# E-Book_v28.net
KiCad netlist of a schematic drawn in EAGLE
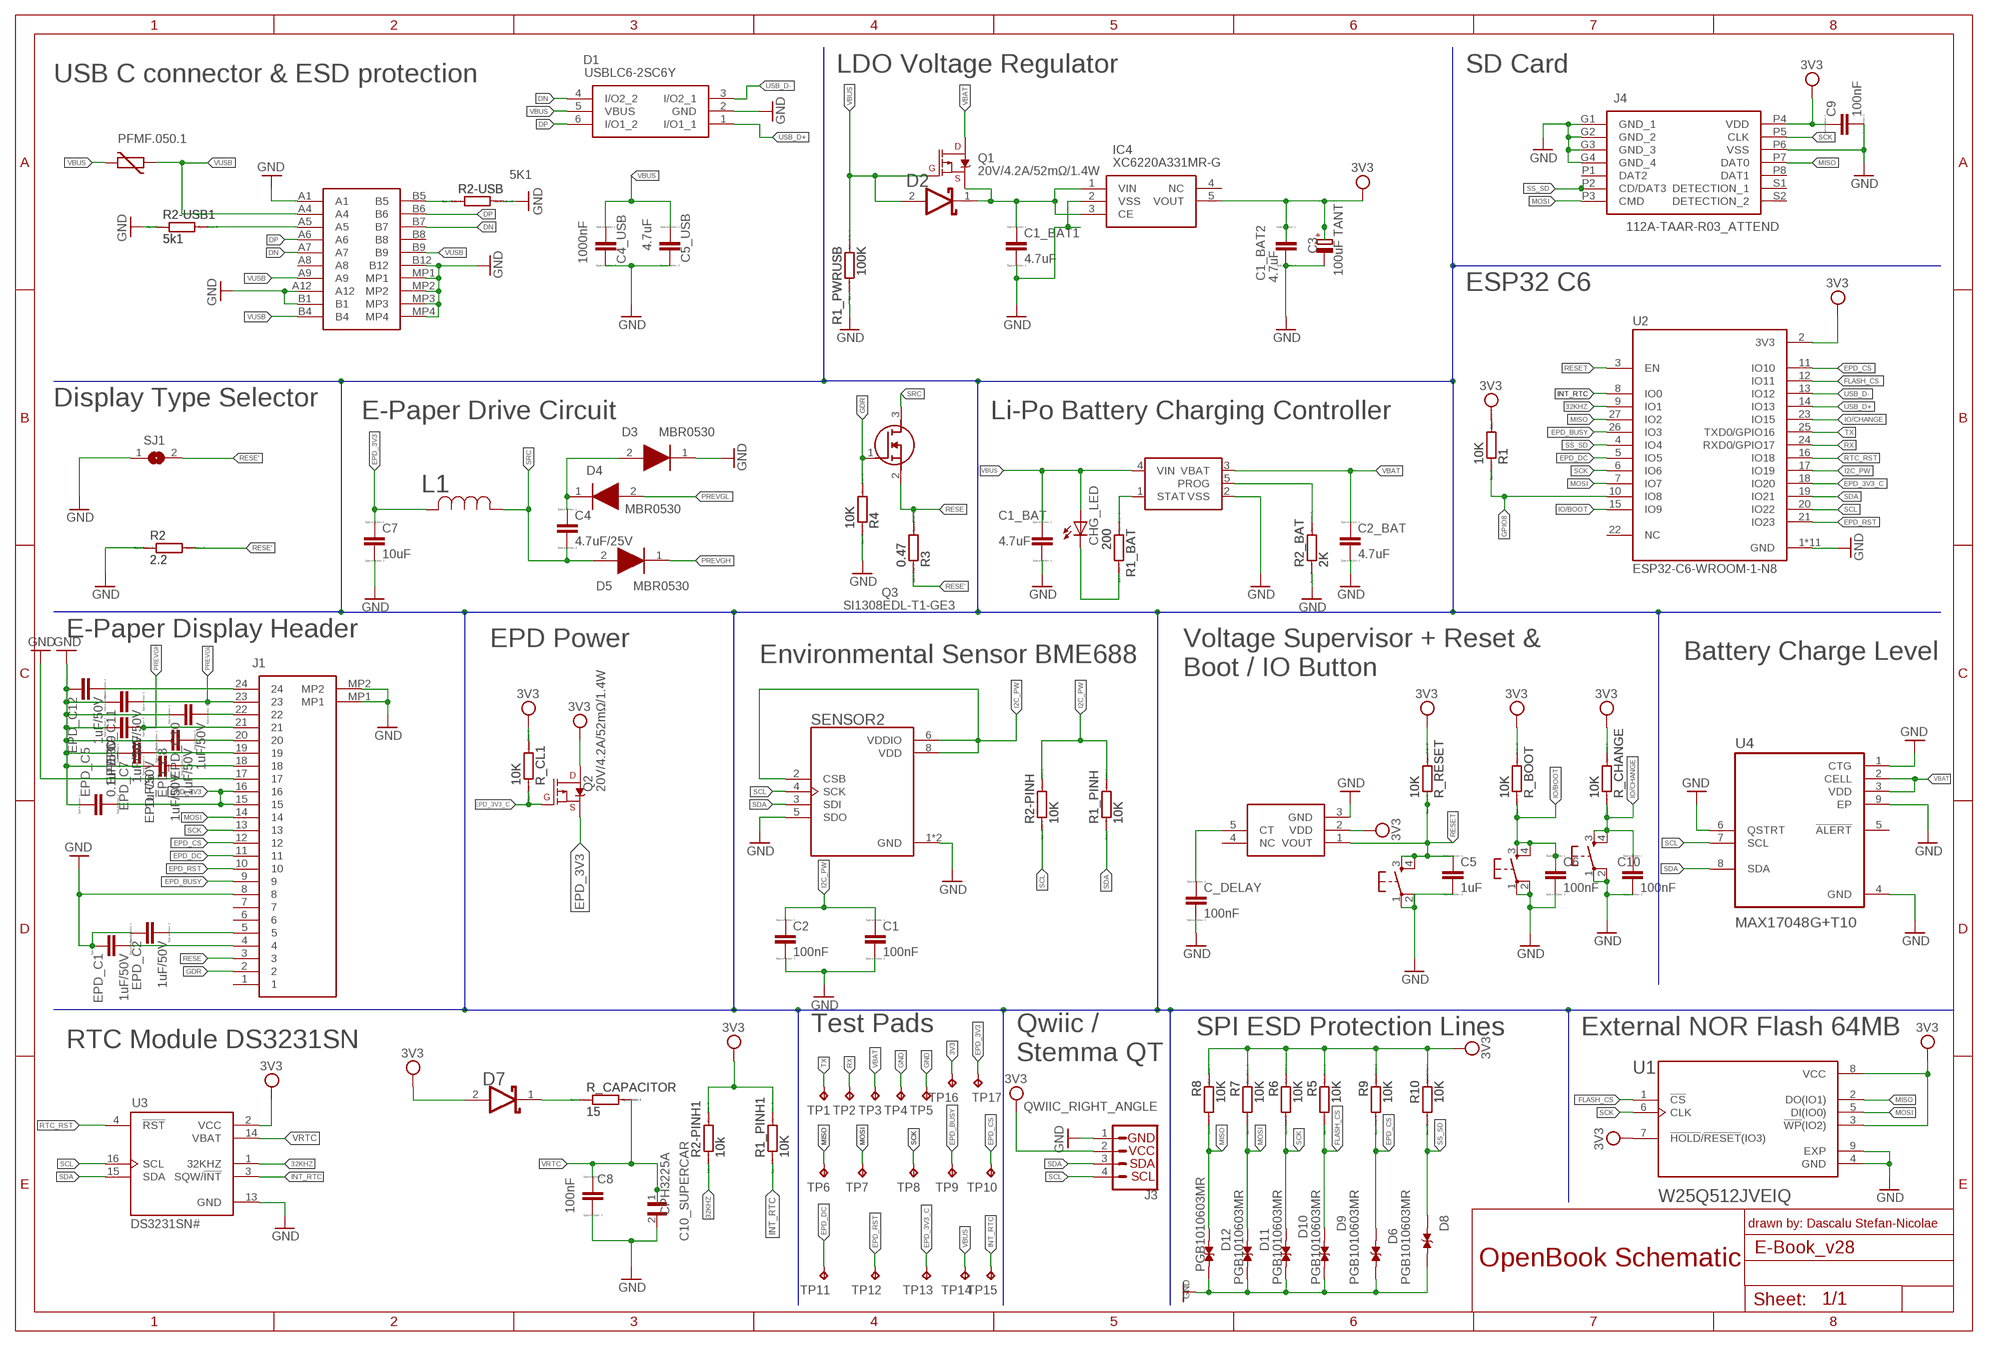
[diagram p0: schematic, sheet 1]

(export (version "E")
  (design (tool "Eeschema 10.0.6"))
  (components
    (comp (ref "C1")
      (value "100nF")
      (footprint "eagle-import:ESP32_WROVER_EAGLE-LTSPICE_C0402")
      (libsource (lib "eagle-import") (part "ESP32_WROVER_EAGLE-LTSPICE_CC0402"))
    )
    (comp (ref "C1_BAT")
      (value "4.7uF")
      (footprint "eagle-import:ESP32_WROVER_EAGLE-LTSPICE_C0402")
      (libsource (lib "eagle-import") (part "ESP32_WROVER_EAGLE-LTSPICE_CC0402"))
    )
    (comp (ref "C1_BAT1")
      (value "4.7uF")
      (footprint "eagle-import:EAGLE-LTSPICE_C0402")
      (libsource (lib "eagle-import") (part "EAGLE-LTSPICE_CC0402"))
    )
    (comp (ref "C1_BAT2")
      (value "4.7uF")
      (footprint "eagle-import:EAGLE-LTSPICE_C0402")
      (libsource (lib "eagle-import") (part "EAGLE-LTSPICE_CC0402"))
    )
    (comp (ref "C2")
      (value "100nF")
      (footprint "eagle-import:ESP32_WROVER_EAGLE-LTSPICE_C0402")
      (libsource (lib "eagle-import") (part "ESP32_WROVER_EAGLE-LTSPICE_CC0402"))
    )
    (comp (ref "C2_BAT")
      (value "4.7uF")
      (footprint "eagle-import:ESP32_WROVER_EAGLE-LTSPICE_C0402")
      (libsource (lib "eagle-import") (part "ESP32_WROVER_EAGLE-LTSPICE_CC0402"))
    )
    (comp (ref "C3")
      (value "100uF TANT")
      (footprint "eagle-import:RCL_CT3528")
      (libsource (lib "eagle-import") (part "RCL_CPOL-EUCT3528"))
    )
    (comp (ref "C4")
      (value "4.7uF/25V")
      (footprint "eagle-import:ESP32_WROVER_EAGLE-LTSPICE_C0402")
      (libsource (lib "eagle-import") (part "ESP32_WROVER_EAGLE-LTSPICE_CC0402"))
    )
    (comp (ref "C4_USB")
      (value "1000nF")
      (footprint "eagle-import:EAGLE-LTSPICE_C0402")
      (libsource (lib "eagle-import") (part "EAGLE-LTSPICE_CC0402"))
    )
    (comp (ref "C5")
      (value "1uF")
      (footprint "eagle-import:ESP32_WROVER_EAGLE-LTSPICE_C0402")
      (libsource (lib "eagle-import") (part "ESP32_WROVER_EAGLE-LTSPICE_CC0402"))
    )
    (comp (ref "C5_USB")
      (value "4.7uF")
      (footprint "eagle-import:EAGLE-LTSPICE_C0402")
      (libsource (lib "eagle-import") (part "EAGLE-LTSPICE_CC0402"))
    )
    (comp (ref "C6")
      (value "100nF")
      (footprint "eagle-import:ESP32_WROVER_EAGLE-LTSPICE_C0402")
      (libsource (lib "eagle-import") (part "ESP32_WROVER_EAGLE-LTSPICE_CC0402"))
    )
    (comp (ref "C7")
      (value "10uF")
      (footprint "eagle-import:ESP32_WROVER_EAGLE-LTSPICE_C0402")
      (libsource (lib "eagle-import") (part "ESP32_WROVER_EAGLE-LTSPICE_CC0402"))
    )
    (comp (ref "C8")
      (value "100nF")
      (footprint "eagle-import:ESP32_WROVER_EAGLE-LTSPICE_C0402")
      (libsource (lib "eagle-import") (part "ESP32_WROVER_EAGLE-LTSPICE_CC0402"))
    )
    (comp (ref "C9")
      (value "100nF")
      (footprint "eagle-import:ESP32_WROVER_EAGLE-LTSPICE_C0402")
      (libsource (lib "eagle-import") (part "ESP32_WROVER_EAGLE-LTSPICE_CC0402"))
    )
    (comp (ref "C10")
      (value "100nF")
      (footprint "eagle-import:ESP32_WROVER_EAGLE-LTSPICE_C0402")
      (libsource (lib "eagle-import") (part "ESP32_WROVER_EAGLE-LTSPICE_CC0402"))
    )
    (comp (ref "C10_SUPERCAR")
      (value "CPH3225A")
      (footprint "eagle-import:CAPCP3225X100N")
      (fields (field (name "MF") "Seiko Instruments"))
      (libsource (lib "eagle-import") (part "CPH3225A"))
    )
    (comp (ref "CHG_LED")
      (value "ADAFRUIT_LEDCHIP-LED0603")
      (footprint "eagle-import:ADAFRUIT_CHIP-LED0603")
      (libsource (lib "eagle-import") (part "ADAFRUIT_LEDCHIP-LED0603"))
    )
    (comp (ref "C_DELAY")
      (value "100nF")
      (footprint "eagle-import:ESP32_WROVER_EAGLE-LTSPICE_C0402")
      (libsource (lib "eagle-import") (part "ESP32_WROVER_EAGLE-LTSPICE_CC0402"))
    )
    (comp (ref "D1")
      (value "USBLC6-2SC6Y")
      (footprint "eagle-import:SOT95P280X145-6N")
      (fields (field (name "MF") "STMicroelectronics"))
      (libsource (lib "eagle-import") (part "USBLC6-2SC6Y"))
    )
    (comp (ref "D2")
      (value "ESP32_WROVER_AVX---SD0805S020S1R0_AVX_SD0805S020S1R0_0_0AVX_SD0805S020S1R0_0_0")
      (footprint "eagle-import:ESP32_WROVER_AVX---SD0805S020S1R0_AVX_SD0805S020S1R0_0")
      (fields
        (field (name "DIGIKEY_PART_NUMBER") "478-7800-1-ND")
        (field (name "MF") "AVX")
        (field (name "MOUSER_PART_NUMBER") "581-SD0805S020S1R0")
      )
      (libsource (lib "eagle-import") (part "ESP32_WROVER_AVX---SD0805S020S1R0_AVX_SD0805S020S1R0_0_0AVX_SD0805S020S1R0_0_0"))
    )
    (comp (ref "D3")
      (value "MBR0530")
      (footprint "eagle-import:SOD3716X135N")
      (fields (field (name "MF") "ON Semiconductor"))
      (libsource (lib "eagle-import") (part "MBR0530"))
    )
    (comp (ref "D4")
      (value "MBR0530")
      (footprint "eagle-import:SOD3716X135N")
      (fields (field (name "MF") "ON Semiconductor"))
      (libsource (lib "eagle-import") (part "MBR0530"))
    )
    (comp (ref "D5")
      (value "MBR0530")
      (footprint "eagle-import:SOD3716X135N")
      (fields (field (name "MF") "ON Semiconductor"))
      (libsource (lib "eagle-import") (part "MBR0530"))
    )
    (comp (ref "D6")
      (value "PGB1010603MR")
      (footprint "eagle-import:DIOC1608X36N")
      (fields (field (name "MF") "Littelfuse Inc."))
      (libsource (lib "eagle-import") (part "PGB1010603MR"))
    )
    (comp (ref "D7")
      (value "ESP32_WROVER_AVX---SD0805S020S1R0_AVX_SD0805S020S1R0_0_0AVX_SD0805S020S1R0_0_0")
      (footprint "eagle-import:ESP32_WROVER_AVX---SD0805S020S1R0_AVX_SD0805S020S1R0_0")
      (fields
        (field (name "DIGIKEY_PART_NUMBER") "478-7800-1-ND")
        (field (name "MF") "AVX")
        (field (name "MOUSER_PART_NUMBER") "581-SD0805S020S1R0")
      )
      (libsource (lib "eagle-import") (part "ESP32_WROVER_AVX---SD0805S020S1R0_AVX_SD0805S020S1R0_0_0AVX_SD0805S020S1R0_0_0"))
    )
    (comp (ref "D8")
      (value "PGB1010603MR")
      (footprint "eagle-import:DIOC1608X36N")
      (fields (field (name "MF") "Littelfuse Inc."))
      (libsource (lib "eagle-import") (part "PGB1010603MR"))
    )
    (comp (ref "D9")
      (value "PGB1010603MR")
      (footprint "eagle-import:DIOC1608X36N")
      (fields (field (name "MF") "Littelfuse Inc."))
      (libsource (lib "eagle-import") (part "PGB1010603MR"))
    )
    (comp (ref "D10")
      (value "PGB1010603MR")
      (footprint "eagle-import:DIOC1608X36N")
      (fields (field (name "MF") "Littelfuse Inc."))
      (libsource (lib "eagle-import") (part "PGB1010603MR"))
    )
    (comp (ref "D11")
      (value "PGB1010603MR")
      (footprint "eagle-import:DIOC1608X36N")
      (fields (field (name "MF") "Littelfuse Inc."))
      (libsource (lib "eagle-import") (part "PGB1010603MR"))
    )
    (comp (ref "D12")
      (value "PGB1010603MR")
      (footprint "eagle-import:DIOC1608X36N")
      (fields (field (name "MF") "Littelfuse Inc."))
      (libsource (lib "eagle-import") (part "PGB1010603MR"))
    )
    (comp (ref "EPD_C1")
      (value "1uF/50V")
      (footprint "eagle-import:ESP32_WROVER_EAGLE-LTSPICE_C0402")
      (libsource (lib "eagle-import") (part "ESP32_WROVER_EAGLE-LTSPICE_CC0402"))
    )
    (comp (ref "EPD_C2")
      (value "1uF/50V")
      (footprint "eagle-import:ESP32_WROVER_EAGLE-LTSPICE_C0402")
      (libsource (lib "eagle-import") (part "ESP32_WROVER_EAGLE-LTSPICE_CC0402"))
    )
    (comp (ref "EPD_C5")
      (value "0.1uF/50V")
      (footprint "eagle-import:ESP32_WROVER_EAGLE-LTSPICE_C0402")
      (libsource (lib "eagle-import") (part "ESP32_WROVER_EAGLE-LTSPICE_CC0402"))
    )
    (comp (ref "EPD_C6")
      (value "1uF/50V")
      (footprint "eagle-import:ESP32_WROVER_EAGLE-LTSPICE_C0402")
      (libsource (lib "eagle-import") (part "ESP32_WROVER_EAGLE-LTSPICE_CC0402"))
    )
    (comp (ref "EPD_C7")
      (value "1uF/50V")
      (footprint "eagle-import:ESP32_WROVER_EAGLE-LTSPICE_C0402")
      (libsource (lib "eagle-import") (part "ESP32_WROVER_EAGLE-LTSPICE_CC0402"))
    )
    (comp (ref "EPD_C8")
      (value "1uF/50V")
      (footprint "eagle-import:ESP32_WROVER_EAGLE-LTSPICE_C0402")
      (libsource (lib "eagle-import") (part "ESP32_WROVER_EAGLE-LTSPICE_CC0402"))
    )
    (comp (ref "EPD_C9")
      (value "1uF/50V")
      (footprint "eagle-import:ESP32_WROVER_EAGLE-LTSPICE_C0402")
      (libsource (lib "eagle-import") (part "ESP32_WROVER_EAGLE-LTSPICE_CC0402"))
    )
    (comp (ref "EPD_C10")
      (value "1uF/50V")
      (footprint "eagle-import:ESP32_WROVER_EAGLE-LTSPICE_C0402")
      (libsource (lib "eagle-import") (part "ESP32_WROVER_EAGLE-LTSPICE_CC0402"))
    )
    (comp (ref "EPD_C11")
      (value "1uF/50V")
      (footprint "eagle-import:ESP32_WROVER_EAGLE-LTSPICE_C0402")
      (libsource (lib "eagle-import") (part "ESP32_WROVER_EAGLE-LTSPICE_CC0402"))
    )
    (comp (ref "EPD_C12")
      (value "1uF/50V")
      (footprint "eagle-import:ESP32_WROVER_EAGLE-LTSPICE_C0402")
      (libsource (lib "eagle-import") (part "ESP32_WROVER_EAGLE-LTSPICE_CC0402"))
    )
    (comp (ref "IC1")
      (value "BD5229G-TR")
      (footprint "eagle-import:SOT95P280X125-5N")
      (fields (field (name "MOUSER_PART_NUMBER") "755-BD5229G-TR"))
      (libsource (lib "eagle-import") (part "BD5229G-TR"))
    )
    (comp (ref "IC4")
      (value "XC6220A331MR-G")
      (footprint "eagle-import:SOT95P280X120-5N")
      (fields (field (name "MOUSER_PART_NUMBER") "865-XC6220A331MR-G"))
      (libsource (lib "eagle-import") (part "XC6220A331MR-G"))
    )
    (comp (ref "J1")
      (value "FH34SRJ-24S-0.5SH_99_")
      (footprint "eagle-import:FH34SRJ24S05SH99")
      (fields
        (field (name "MANUFACTURER_PART_NUMBER") "FH34SRJ-24S-0.5SH(99)")
        (field (name "MOUSER_PART_NUMBER") "798-FH34SRJ24S05SH99")
      )
      (libsource (lib "eagle-import") (part "FH34SRJ-24S-0.5SH_99_"))
    )
    (comp (ref "J2")
      (value "SAMACSYS_PARTS_USB4110-GF-A")
      (footprint "eagle-import:SAMACSYS_PARTS_USB4110GFA")
      (fields
        (field (name "MANUFACTURER_PART_NUMBER") "USB4110-GF-A")
        (field (name "MOUSER_PART_NUMBER") "640-USB4110-GF-A")
      )
      (libsource (lib "eagle-import") (part "SAMACSYS_PARTS_USB4110-GF-A"))
    )
    (comp (ref "J3")
      (value "QWIIC_RIGHT_ANGLE")
      (footprint "eagle-import:JST04_1MM_RA")
      (libsource (lib "eagle-import") (part "QWIIC_CONNECTORJS-1MM"))
    )
    (comp (ref "J4")
      (value "112A-TAAR-R03_ATTEND")
      (footprint "eagle-import:112ATAARR03ATTEND")
      (fields (field (name "MANUFACTURER_PART_NUMBER") "112A-TAAR-R03 ATTEND"))
      (libsource (lib "eagle-import") (part "112A-TAAR-R03_ATTEND"))
    )
    (comp (ref "L1")
      (value "744043680IND_4828-WE-TPC_WRE")
      (footprint "eagle-import:IND_4828-WE-TPC_WRE")
      (fields
        (field (name "MANUFACTURER_PART_NUMBER") "744043680")
        (field (name "COPYRIGHT") "Copyright (C) 2024 Ultra Librarian. All rights reserved.")
      )
      (libsource (lib "eagle-import") (part "744043680IND_4828-WE-TPC_WRE"))
    )
    (comp (ref "MCP73831")
      (value "ESP32_WROVER_SPARKFUN-IC-POWER_MCP73831")
      (footprint "eagle-import:ESP32_WROVER_SPARKFUN-IC-POWER_SOT23-5")
      (libsource (lib "eagle-import") (part "ESP32_WROVER_SPARKFUN-IC-POWER_MCP73831"))
    )
    (comp (ref "PFMF.050.1")
      (value "ESP32C6_VARISTORCN1812")
      (footprint "eagle-import:ESP32C6_VARISTOR_CT_CN1812")
      (libsource (lib "eagle-import") (part "ESP32C6_VARISTORCN1812"))
    )
    (comp (ref "Q1")
      (value "20V/4.2A/52mΩ/1.4W")
      (footprint "eagle-import:ESP32_WROVER_SPARKFUN-DISCRETESEMI_SOT23-3")
      (libsource (lib "eagle-import") (part "ESP32_WROVER_SPARKFUN-DISCRETESEMI_MOSFET_PCH-DMG2305UX-7"))
    )
    (comp (ref "Q2")
      (value "20V/4.2A/52mΩ/1.4W")
      (footprint "eagle-import:ESP32_WROVER_SPARKFUN-DISCRETESEMI_SOT23-3")
      (libsource (lib "eagle-import") (part "ESP32_WROVER_SPARKFUN-DISCRETESEMI_MOSFET_PCH-DMG2305UX-7"))
    )
    (comp (ref "Q3")
      (value "SI1308EDL-T1-GE3")
      (footprint "eagle-import:SOT65P210X110-3N")
      (fields (field (name "MF") "Vishay Siliconix"))
      (libsource (lib "eagle-import") (part "SI1308EDL-T1-GE3"))
    )
    (comp (ref "R1")
      (value "10K")
      (footprint "eagle-import:ESP32_WROVER_EAGLE-LTSPICE_R0402")
      (libsource (lib "eagle-import") (part "ESP32_WROVER_EAGLE-LTSPICE_RR0402"))
    )
    (comp (ref "R1_BAT")
      (value "200")
      (footprint "eagle-import:ESP32_WROVER_EAGLE-LTSPICE_R0402")
      (libsource (lib "eagle-import") (part "ESP32_WROVER_EAGLE-LTSPICE_RR0402"))
    )
    (comp (ref "R1_PINH")
      (value "10K")
      (footprint "eagle-import:ESP32_WROVER_EAGLE-LTSPICE_R0402")
      (libsource (lib "eagle-import") (part "ESP32_WROVER_EAGLE-LTSPICE_RR0402"))
    )
    (comp (ref "R1_PINH1")
      (value "10K")
      (footprint "eagle-import:ESP32_WROVER_EAGLE-LTSPICE_R0402")
      (libsource (lib "eagle-import") (part "ESP32_WROVER_EAGLE-LTSPICE_RR0402"))
    )
    (comp (ref "R1_PWRUSB")
      (value "100K")
      (footprint "eagle-import:ESP32_WROVER_EAGLE-LTSPICE_R0402")
      (libsource (lib "eagle-import") (part "ESP32_WROVER_EAGLE-LTSPICE_RR0402"))
    )
    (comp (ref "R2")
      (value "2.2")
      (footprint "eagle-import:ESP32_WROVER_EAGLE-LTSPICE_R0402")
      (libsource (lib "eagle-import") (part "ESP32_WROVER_EAGLE-LTSPICE_RR0402"))
    )
    (comp (ref "R2-PINH")
      (value "10K")
      (footprint "eagle-import:ESP32_WROVER_EAGLE-LTSPICE_R0402")
      (libsource (lib "eagle-import") (part "ESP32_WROVER_EAGLE-LTSPICE_RR0402"))
    )
    (comp (ref "R2-PINH1")
      (value "10k")
      (footprint "eagle-import:ESP32_WROVER_EAGLE-LTSPICE_R0402")
      (libsource (lib "eagle-import") (part "ESP32_WROVER_EAGLE-LTSPICE_RR0402"))
    )
    (comp (ref "R2-USB")
      (value "5K1")
      (footprint "eagle-import:ESP32_WROVER_EAGLE-LTSPICE_R0402")
      (libsource (lib "eagle-import") (part "ESP32_WROVER_EAGLE-LTSPICE_RR0402"))
    )
    (comp (ref "R2-USB1")
      (value "5k1")
      (footprint "eagle-import:ESP32_WROVER_EAGLE-LTSPICE_R0402")
      (libsource (lib "eagle-import") (part "ESP32_WROVER_EAGLE-LTSPICE_RR0402"))
    )
    (comp (ref "R2_BAT")
      (value "2K")
      (footprint "eagle-import:ESP32_WROVER_EAGLE-LTSPICE_R0402")
      (libsource (lib "eagle-import") (part "ESP32_WROVER_EAGLE-LTSPICE_RR0402"))
    )
    (comp (ref "R3")
      (value "0.47")
      (footprint "eagle-import:ESP32_WROVER_EAGLE-LTSPICE_R0402")
      (libsource (lib "eagle-import") (part "ESP32_WROVER_EAGLE-LTSPICE_RR0402"))
    )
    (comp (ref "R4")
      (value "10K")
      (footprint "eagle-import:ESP32_WROVER_EAGLE-LTSPICE_R0402")
      (libsource (lib "eagle-import") (part "ESP32_WROVER_EAGLE-LTSPICE_RR0402"))
    )
    (comp (ref "R5")
      (value "10K")
      (footprint "eagle-import:ESP32_WROVER_EAGLE-LTSPICE_R0402")
      (libsource (lib "eagle-import") (part "ESP32_WROVER_EAGLE-LTSPICE_RR0402"))
    )
    (comp (ref "R6")
      (value "10K")
      (footprint "eagle-import:ESP32_WROVER_EAGLE-LTSPICE_R0402")
      (libsource (lib "eagle-import") (part "ESP32_WROVER_EAGLE-LTSPICE_RR0402"))
    )
    (comp (ref "R7")
      (value "10K")
      (footprint "eagle-import:ESP32_WROVER_EAGLE-LTSPICE_R0402")
      (libsource (lib "eagle-import") (part "ESP32_WROVER_EAGLE-LTSPICE_RR0402"))
    )
    (comp (ref "R8")
      (value "10K")
      (footprint "eagle-import:ESP32_WROVER_EAGLE-LTSPICE_R0402")
      (libsource (lib "eagle-import") (part "ESP32_WROVER_EAGLE-LTSPICE_RR0402"))
    )
    (comp (ref "R9")
      (value "10K")
      (footprint "eagle-import:ESP32_WROVER_EAGLE-LTSPICE_R0402")
      (libsource (lib "eagle-import") (part "ESP32_WROVER_EAGLE-LTSPICE_RR0402"))
    )
    (comp (ref "R10")
      (value "10K")
      (footprint "eagle-import:ESP32_WROVER_EAGLE-LTSPICE_R0402")
      (libsource (lib "eagle-import") (part "ESP32_WROVER_EAGLE-LTSPICE_RR0402"))
    )
    (comp (ref "RESET_BUTTON")
      (value "BUTTON_CUSYOMV1")
      (footprint "eagle-import:MYBUTTON")
      (libsource (lib "eagle-import") (part "BUTTON_CUSYOMV1"))
    )
    (comp (ref "R_BOOT")
      (value "10K")
      (footprint "eagle-import:ESP32_WROVER_EAGLE-LTSPICE_R0402")
      (libsource (lib "eagle-import") (part "ESP32_WROVER_EAGLE-LTSPICE_RR0402"))
    )
    (comp (ref "R_CAPACITOR")
      (value "15")
      (footprint "eagle-import:ESP32_WROVER_EAGLE-LTSPICE_R0402")
      (libsource (lib "eagle-import") (part "ESP32_WROVER_EAGLE-LTSPICE_RR0402"))
    )
    (comp (ref "R_CHANGE")
      (value "10K")
      (footprint "eagle-import:ESP32_WROVER_EAGLE-LTSPICE_R0402")
      (libsource (lib "eagle-import") (part "ESP32_WROVER_EAGLE-LTSPICE_RR0402"))
    )
    (comp (ref "R_CL1")
      (value "10K")
      (footprint "eagle-import:ESP32_WROVER_EAGLE-LTSPICE_R0402")
      (libsource (lib "eagle-import") (part "ESP32_WROVER_EAGLE-LTSPICE_RR0402"))
    )
    (comp (ref "R_RESET")
      (value "10K")
      (footprint "eagle-import:ESP32_WROVER_EAGLE-LTSPICE_R0402")
      (libsource (lib "eagle-import") (part "ESP32_WROVER_EAGLE-LTSPICE_RR0402"))
    )
    (comp (ref "SENSOR2")
      (value "ESP32_WROVER_BME680_BME680")
      (footprint "eagle-import:ESP32_WROVER_BME680_PSON80P300X300X100-8N")
      (fields (field (name "MF") "Bosch Sensortec") (field (name "MP") "BME680"))
      (libsource (lib "eagle-import") (part "ESP32_WROVER_BME680_BME680"))
    )
    (comp (ref "SJ1") (value "SJ") (footprint "eagle-import:SJ") (libsource (lib "eagle-import") (part "SJ")))
    (comp (ref "TP1")
      (value "TPTP20R")
      (footprint "eagle-import:TP20R")
      (libsource (lib "eagle-import") (part "TPTP20R"))
    )
    (comp (ref "TP2")
      (value "TPTP20R")
      (footprint "eagle-import:TP20R")
      (libsource (lib "eagle-import") (part "TPTP20R"))
    )
    (comp (ref "TP3")
      (value "TPTP20R")
      (footprint "eagle-import:TP20R")
      (libsource (lib "eagle-import") (part "TPTP20R"))
    )
    (comp (ref "TP4")
      (value "TPTP20R")
      (footprint "eagle-import:TP20R")
      (libsource (lib "eagle-import") (part "TPTP20R"))
    )
    (comp (ref "TP5")
      (value "TPTP20R")
      (footprint "eagle-import:TP20R")
      (libsource (lib "eagle-import") (part "TPTP20R"))
    )
    (comp (ref "TP6")
      (value "TPTP20R")
      (footprint "eagle-import:TP20R")
      (libsource (lib "eagle-import") (part "TPTP20R"))
    )
    (comp (ref "TP7")
      (value "TPTP20R")
      (footprint "eagle-import:TP20R")
      (libsource (lib "eagle-import") (part "TPTP20R"))
    )
    (comp (ref "TP8")
      (value "TPTP20R")
      (footprint "eagle-import:TP20R")
      (libsource (lib "eagle-import") (part "TPTP20R"))
    )
    (comp (ref "TP9")
      (value "TPTP20R")
      (footprint "eagle-import:TP20R")
      (libsource (lib "eagle-import") (part "TPTP20R"))
    )
    (comp (ref "TP10")
      (value "TPTP20R")
      (footprint "eagle-import:TP20R")
      (libsource (lib "eagle-import") (part "TPTP20R"))
    )
    (comp (ref "TP11")
      (value "TPTP20R")
      (footprint "eagle-import:TP20R")
      (libsource (lib "eagle-import") (part "TPTP20R"))
    )
    (comp (ref "TP12")
      (value "TPTP20R")
      (footprint "eagle-import:TP20R")
      (libsource (lib "eagle-import") (part "TPTP20R"))
    )
    (comp (ref "TP13")
      (value "TPTP20R")
      (footprint "eagle-import:TP20R")
      (libsource (lib "eagle-import") (part "TPTP20R"))
    )
    (comp (ref "TP14")
      (value "TPTP20R")
      (footprint "eagle-import:TP20R")
      (libsource (lib "eagle-import") (part "TPTP20R"))
    )
    (comp (ref "TP15")
      (value "TPTP20R")
      (footprint "eagle-import:TP20R")
      (libsource (lib "eagle-import") (part "TPTP20R"))
    )
    (comp (ref "TP16")
      (value "TPTP20R")
      (footprint "eagle-import:TP20R")
      (libsource (lib "eagle-import") (part "TPTP20R"))
    )
    (comp (ref "TP17")
      (value "TPTP20R")
      (footprint "eagle-import:TP20R")
      (libsource (lib "eagle-import") (part "TPTP20R"))
    )
    (comp (ref "U$1")
      (value "BUTTON_CUSYOMV1")
      (footprint "eagle-import:MYBUTTON")
      (libsource (lib "eagle-import") (part "BUTTON_CUSYOMV1"))
    )
    (comp (ref "U$3")
      (value "BUTTON_CUSYOMV1")
      (footprint "eagle-import:MYBUTTON")
      (libsource (lib "eagle-import") (part "BUTTON_CUSYOMV1"))
    )
    (comp (ref "U1")
      (value "W25Q512JVEIQ")
      (footprint "eagle-import:SON127P600X800X80-9N")
      (fields (field (name "MF") "Winbond Electronics"))
      (libsource (lib "eagle-import") (part "W25Q512JVEIQ"))
    )
    (comp (ref "U2")
      (value "ESP32-C6-WROOM-1-N8")
      (footprint "eagle-import:XCVR_ESP32-C6-WROOM-1-N8")
      (fields (field (name "MF") "Espressif Systems"))
      (libsource (lib "eagle-import") (part "ESP32-C6-WROOM-1-N8"))
    )
    (comp (ref "U3")
      (value "DS3231SN#")
      (footprint "eagle-import:SOIC127P1032X265-16N")
      (fields (field (name "MF") "Analog Devices"))
      (libsource (lib "eagle-import") (part "DS3231SN#"))
    )
    (comp (ref "U4")
      (value "MAX17048G+T10")
      (footprint "eagle-import:SON50P200X200X80-9N")
      (fields (field (name "MF") "Analog Devices"))
      (libsource (lib "eagle-import") (part "MAX17048G+T10"))
    )
  )
  (nets
    (net (code "1") (name "3V3") (class "Default")
      (node (ref "C1_BAT2") (pin "1") (pinfunction "1_1") (pintype "passive"))
      (node (ref "C3") (pin "+") (pinfunction "+_+") (pintype "passive"))
      (node (ref "C9") (pin "1") (pinfunction "1_1") (pintype "passive"))
      (node (ref "D7") (pin "2") (pinfunction "ANODE_2") (pintype "bidirectional"))
      (node (ref "IC1") (pin "2") (pinfunction "VDD_2") (pintype "bidirectional"))
      (node (ref "IC4") (pin "5") (pinfunction "VOUT_5") (pintype "bidirectional"))
      (node (ref "J3") (pin "2") (pinfunction "2_2") (pintype "power_in"))
      (node (ref "J4") (pin "P4") (pinfunction "VDD_P4") (pintype "bidirectional"))
      (node (ref "Q2") (pin "3") (pinfunction "D_3") (pintype "bidirectional"))
      (node (ref "R1") (pin "2") (pinfunction "2_2") (pintype "passive"))
      (node (ref "R10") (pin "1") (pinfunction "1_1") (pintype "passive"))
      (node (ref "R1_PINH1") (pin "2") (pinfunction "2_2") (pintype "passive"))
      (node (ref "R2-PINH1") (pin "2") (pinfunction "2_2") (pintype "passive"))
      (node (ref "R5") (pin "1") (pinfunction "1_1") (pintype "passive"))
      (node (ref "R6") (pin "1") (pinfunction "1_1") (pintype "passive"))
      (node (ref "R7") (pin "1") (pinfunction "1_1") (pintype "passive"))
      (node (ref "R8") (pin "1") (pinfunction "1_1") (pintype "passive"))
      (node (ref "R9") (pin "1") (pinfunction "1_1") (pintype "passive"))
      (node (ref "R_BOOT") (pin "2") (pinfunction "2_2") (pintype "passive"))
      (node (ref "R_CHANGE") (pin "2") (pinfunction "2_2") (pintype "passive"))
      (node (ref "R_CL1") (pin "2") (pinfunction "2_2") (pintype "passive"))
      (node (ref "R_RESET") (pin "2") (pinfunction "2_2") (pintype "passive"))
      (node (ref "TP16") (pin "TP") (pinfunction "TP_TP") (pintype "input"))
      (node (ref "U1") (pin "3") (pinfunction "~{WP}(IO2)_3") (pintype "bidirectional"))
      (node (ref "U1") (pin "7") (pinfunction "~{HOLD}/~{RESET}(IO3)_7") (pintype "bidirectional"))
      (node (ref "U1") (pin "8") (pinfunction "VCC_8") (pintype "power_in"))
      (node (ref "U2") (pin "2") (pinfunction "3V3_2") (pintype "power_in"))
      (node (ref "U3") (pin "2") (pinfunction "VCC_2") (pintype "power_in"))
    )
    (net (code "2") (name "32KHZ") (class "Default")
      (node (ref "R2-PINH1") (pin "1") (pinfunction "1_1") (pintype "passive"))
      (node (ref "U2") (pin "9") (pinfunction "IO1_9") (pintype "bidirectional"))
      (node (ref "U3") (pin "1") (pinfunction "32KHZ_1") (pintype "output"))
    )
    (net (code "3") (name "DN") (class "Default")
      (node (ref "D1") (pin "4") (pinfunction "I/O2_2_4") (pintype "bidirectional"))
      (node (ref "J2") (pin "A7") (pinfunction "A7_A7") (pintype "bidirectional"))
      (node (ref "J2") (pin "B7") (pinfunction "B7_B7") (pintype "bidirectional"))
    )
    (net (code "4") (name "DP") (class "Default")
      (node (ref "D1") (pin "6") (pinfunction "I/O1_2_6") (pintype "bidirectional"))
      (node (ref "J2") (pin "A6") (pinfunction "A6_A6") (pintype "bidirectional"))
      (node (ref "J2") (pin "B6") (pinfunction "B6_B6") (pintype "bidirectional"))
    )
    (net (code "5") (name "EPD_3V3") (class "Default")
      (node (ref "C7") (pin "1") (pinfunction "1_1") (pintype "passive"))
      (node (ref "EPD_C5") (pin "2") (pinfunction "2_2") (pintype "passive"))
      (node (ref "J1") (pin "15") (pinfunction "15_15") (pintype "bidirectional"))
      (node (ref "J1") (pin "16") (pinfunction "16_16") (pintype "bidirectional"))
      (node (ref "L1") (pin "2") (pinfunction "2_2") (pintype "passive"))
      (node (ref "Q2") (pin "2") (pinfunction "S_2") (pintype "bidirectional"))
      (node (ref "TP17") (pin "TP") (pinfunction "TP_TP") (pintype "input"))
    )
    (net (code "6") (name "EPD_3V3_C") (class "Default")
      (node (ref "Q2") (pin "1") (pinfunction "G_1") (pintype "bidirectional"))
      (node (ref "R_CL1") (pin "1") (pinfunction "1_1") (pintype "passive"))
      (node (ref "TP13") (pin "TP") (pinfunction "TP_TP") (pintype "input"))
      (node (ref "U2") (pin "18") (pinfunction "IO20_18") (pintype "bidirectional"))
    )
    (net (code "7") (name "EPD_BUSY") (class "Default")
      (node (ref "J1") (pin "9") (pinfunction "9_9") (pintype "bidirectional"))
      (node (ref "TP9") (pin "TP") (pinfunction "TP_TP") (pintype "input"))
      (node (ref "U2") (pin "26") (pinfunction "IO3_26") (pintype "bidirectional"))
    )
    (net (code "8") (name "EPD_CS") (class "Default")
      (node (ref "D6") (pin "1") (pinfunction "1_1") (pintype "passive"))
      (node (ref "J1") (pin "12") (pinfunction "12_12") (pintype "bidirectional"))
      (node (ref "R9") (pin "2") (pinfunction "2_2") (pintype "passive"))
      (node (ref "TP10") (pin "TP") (pinfunction "TP_TP") (pintype "input"))
      (node (ref "U2") (pin "11") (pinfunction "IO10_11") (pintype "bidirectional"))
    )
    (net (code "9") (name "EPD_DC") (class "Default")
      (node (ref "J1") (pin "11") (pinfunction "11_11") (pintype "bidirectional"))
      (node (ref "TP11") (pin "TP") (pinfunction "TP_TP") (pintype "input"))
      (node (ref "U2") (pin "5") (pinfunction "IO5_5") (pintype "bidirectional"))
    )
    (net (code "10") (name "EPD_RST") (class "Default")
      (node (ref "J1") (pin "10") (pinfunction "10_10") (pintype "bidirectional"))
      (node (ref "TP12") (pin "TP") (pinfunction "TP_TP") (pintype "input"))
      (node (ref "U2") (pin "21") (pinfunction "IO23_21") (pintype "bidirectional"))
    )
    (net (code "11") (name "FLASH_CS") (class "Default")
      (node (ref "D9") (pin "1") (pinfunction "1_1") (pintype "passive"))
      (node (ref "R5") (pin "2") (pinfunction "2_2") (pintype "passive"))
      (node (ref "U1") (pin "1") (pinfunction "~{CS}_1") (pintype "input"))
      (node (ref "U2") (pin "12") (pinfunction "IO11_12") (pintype "bidirectional"))
    )
    (net (code "12") (name "GDR") (class "Default")
      (node (ref "J1") (pin "2") (pinfunction "2_2") (pintype "bidirectional"))
      (node (ref "Q3") (pin "1") (pinfunction "G_1") (pintype "bidirectional"))
      (node (ref "R4") (pin "2") (pinfunction "2_2") (pintype "passive"))
    )
    (net (code "13") (name "GND") (class "Default")
      (node (ref "C1") (pin "2") (pinfunction "2_2") (pintype "passive"))
      (node (ref "C10") (pin "2") (pinfunction "2_2") (pintype "passive"))
      (node (ref "C10_SUPERCAR") (pin "2") (pinfunction "2_2") (pintype "passive"))
      (node (ref "C1_BAT") (pin "2") (pinfunction "2_2") (pintype "passive"))
      (node (ref "C1_BAT1") (pin "2") (pinfunction "2_2") (pintype "passive"))
      (node (ref "C1_BAT2") (pin "2") (pinfunction "2_2") (pintype "passive"))
      (node (ref "C2") (pin "2") (pinfunction "2_2") (pintype "passive"))
      (node (ref "C2_BAT") (pin "2") (pinfunction "2_2") (pintype "passive"))
      (node (ref "C3") (pin "-") (pinfunction "-_-") (pintype "passive"))
      (node (ref "C4_USB") (pin "2") (pinfunction "2_2") (pintype "passive"))
      (node (ref "C5") (pin "2") (pinfunction "2_2") (pintype "passive"))
      (node (ref "C5_USB") (pin "2") (pinfunction "2_2") (pintype "passive"))
      (node (ref "C6") (pin "2") (pinfunction "2_2") (pintype "passive"))
      (node (ref "C7") (pin "2") (pinfunction "2_2") (pintype "passive"))
      (node (ref "C8") (pin "2") (pinfunction "2_2") (pintype "passive"))
      (node (ref "C9") (pin "2") (pinfunction "2_2") (pintype "passive"))
      (node (ref "C_DELAY") (pin "2") (pinfunction "2_2") (pintype "passive"))
      (node (ref "D1") (pin "2") (pinfunction "GND_2") (pintype "bidirectional"))
      (node (ref "D10") (pin "2") (pinfunction "2_2") (pintype "passive"))
      (node (ref "D11") (pin "2") (pinfunction "2_2") (pintype "passive"))
      (node (ref "D12") (pin "2") (pinfunction "2_2") (pintype "passive"))
      (node (ref "D3") (pin "1") (pinfunction "K_1") (pintype "bidirectional"))
      (node (ref "D6") (pin "2") (pinfunction "2_2") (pintype "passive"))
      (node (ref "D8") (pin "2") (pinfunction "2_2") (pintype "passive"))
      (node (ref "D9") (pin "2") (pinfunction "2_2") (pintype "passive"))
      (node (ref "EPD_C1") (pin "1") (pinfunction "1_1") (pintype "passive"))
      (node (ref "EPD_C10") (pin "1") (pinfunction "1_1") (pintype "passive"))
      (node (ref "EPD_C11") (pin "1") (pinfunction "1_1") (pintype "passive"))
      (node (ref "EPD_C12") (pin "1") (pinfunction "1_1") (pintype "passive"))
      (node (ref "EPD_C2") (pin "1") (pinfunction "1_1") (pintype "passive"))
      (node (ref "EPD_C5") (pin "1") (pinfunction "1_1") (pintype "passive"))
      (node (ref "EPD_C6") (pin "1") (pinfunction "1_1") (pintype "passive"))
      (node (ref "EPD_C7") (pin "1") (pinfunction "1_1") (pintype "passive"))
      (node (ref "EPD_C8") (pin "1") (pinfunction "1_1") (pintype "passive"))
      (node (ref "EPD_C9") (pin "1") (pinfunction "1_1") (pintype "passive"))
      (node (ref "IC1") (pin "3") (pinfunction "GND_3") (pintype "bidirectional"))
      (node (ref "IC4") (pin "2") (pinfunction "VSS_2") (pintype "bidirectional"))
      (node (ref "J1") (pin "17") (pinfunction "17_17") (pintype "bidirectional"))
      (node (ref "J1") (pin "8") (pinfunction "8_8") (pintype "bidirectional"))
      (node (ref "J1") (pin "MP1") (pinfunction "MP1_MP1") (pintype "bidirectional"))
      (node (ref "J1") (pin "MP2") (pinfunction "MP2_MP2") (pintype "bidirectional"))
      (node (ref "J2") (pin "A1") (pinfunction "A1_A1") (pintype "bidirectional"))
      (node (ref "J2") (pin "A12") (pinfunction "A12_A12") (pintype "bidirectional"))
      (node (ref "J2") (pin "B1") (pinfunction "B1_B1") (pintype "bidirectional"))
      (node (ref "J2") (pin "B12") (pinfunction "B12_B12") (pintype "bidirectional"))
      (node (ref "J2") (pin "MP1") (pinfunction "MP1_MP1") (pintype "bidirectional"))
      (node (ref "J2") (pin "MP2") (pinfunction "MP2_MP2") (pintype "bidirectional"))
      (node (ref "J2") (pin "MP3") (pinfunction "MP3_MP3") (pintype "bidirectional"))
      (node (ref "J2") (pin "MP4") (pinfunction "MP4_MP4") (pintype "bidirectional"))
      (node (ref "J3") (pin "1") (pinfunction "1_1") (pintype "power_in"))
      (node (ref "J4") (pin "G1") (pinfunction "GND_1_G1") (pintype "bidirectional"))
      (node (ref "J4") (pin "G2") (pinfunction "GND_2_G2") (pintype "bidirectional"))
      (node (ref "J4") (pin "G3") (pinfunction "GND_3_G3") (pintype "bidirectional"))
      (node (ref "J4") (pin "G4") (pinfunction "GND_4_G4") (pintype "bidirectional"))
      (node (ref "J4") (pin "P6") (pinfunction "VSS_P6") (pintype "bidirectional"))
      (node (ref "MCP73831") (pin "2") (pinfunction "VSS_2") (pintype "power_in"))
      (node (ref "R1_PWRUSB") (pin "2") (pinfunction "2_2") (pintype "passive"))
      (node (ref "R2") (pin "1") (pinfunction "1_1") (pintype "passive"))
      (node (ref "R2-USB") (pin "2") (pinfunction "2_2") (pintype "passive"))
      (node (ref "R2-USB1") (pin "1") (pinfunction "1_1") (pintype "passive"))
      (node (ref "R2_BAT") (pin "1") (pinfunction "1_1") (pintype "passive"))
      (node (ref "R4") (pin "1") (pinfunction "1_1") (pintype "passive"))
      (node (ref "RESET_BUTTON") (pin "1") (pinfunction "1_1") (pintype "passive"))
      (node (ref "RESET_BUTTON") (pin "2") (pinfunction "2_2") (pintype "passive"))
      (node (ref "SENSOR2") (pin "1") (pinfunction "GND_1") (pintype "power_in"))
      (node (ref "SENSOR2") (pin "5") (pinfunction "SDO_5") (pintype "bidirectional"))
      (node (ref "SENSOR2") (pin "7") (pinfunction "GND_7") (pintype "power_in"))
      (node (ref "SJ1") (pin "1") (pinfunction "1_1") (pintype "passive"))
      (node (ref "TP4") (pin "TP") (pinfunction "TP_TP") (pintype "input"))
      (node (ref "TP5") (pin "TP") (pinfunction "TP_TP") (pintype "input"))
      (node (ref "U$1") (pin "1") (pinfunction "1_1") (pintype "passive"))
      (node (ref "U$1") (pin "2") (pinfunction "2_2") (pintype "passive"))
      (node (ref "U$3") (pin "1") (pinfunction "1_1") (pintype "passive"))
      (node (ref "U$3") (pin "2") (pinfunction "2_2") (pintype "passive"))
      (node (ref "U1") (pin "4") (pinfunction "GND_4") (pintype "power_in"))
      (node (ref "U1") (pin "9") (pinfunction "EXP_9") (pintype "passive"))
      (node (ref "U2") (pin "1") (pinfunction "GND_1") (pintype "power_in"))
      (node (ref "U2") (pin "28") (pinfunction "GND_28") (pintype "power_in"))
      (node (ref "U2") (pin "29_1") (pinfunction "GND_29_1") (pintype "power_in"))
      (node (ref "U2") (pin "29_2") (pinfunction "GND_29_2") (pintype "power_in"))
      (node (ref "U2") (pin "29_3") (pinfunction "GND_29_3") (pintype "power_in"))
      (node (ref "U2") (pin "29_4") (pinfunction "GND_29_4") (pintype "power_in"))
      (node (ref "U2") (pin "29_5") (pinfunction "GND_29_5") (pintype "power_in"))
      (node (ref "U2") (pin "29_6") (pinfunction "GND_29_6") (pintype "power_in"))
      (node (ref "U2") (pin "29_7") (pinfunction "GND_29_7") (pintype "power_in"))
      (node (ref "U2") (pin "29_8") (pinfunction "GND_29_8") (pintype "power_in"))
      (node (ref "U2") (pin "29_9") (pinfunction "GND_29_9") (pintype "power_in"))
      (node (ref "U3") (pin "13") (pinfunction "GND_13") (pintype "power_in"))
      (node (ref "U4") (pin "1") (pinfunction "CTG_1") (pintype "power_in"))
      (node (ref "U4") (pin "4") (pinfunction "GND_4") (pintype "power_in"))
      (node (ref "U4") (pin "6") (pinfunction "QSTRT_6") (pintype "input"))
      (node (ref "U4") (pin "9") (pinfunction "EP_9") (pintype "power_in"))
    )
    (net (code "14") (name "GPIO8") (class "Default")
      (node (ref "R1") (pin "1") (pinfunction "1_1") (pintype "passive"))
      (node (ref "U2") (pin "10") (pinfunction "IO8_10") (pintype "bidirectional"))
    )
    (net (code "15") (name "I2C_PW") (class "Default")
      (node (ref "C1") (pin "1") (pinfunction "1_1") (pintype "passive"))
      (node (ref "C2") (pin "1") (pinfunction "1_1") (pintype "passive"))
      (node (ref "R1_PINH") (pin "2") (pinfunction "2_2") (pintype "passive"))
      (node (ref "R2-PINH") (pin "2") (pinfunction "2_2") (pintype "passive"))
      (node (ref "SENSOR2") (pin "2") (pinfunction "CSB_2") (pintype "input"))
      (node (ref "SENSOR2") (pin "6") (pinfunction "VDDIO_6") (pintype "power_in"))
      (node (ref "SENSOR2") (pin "8") (pinfunction "VDD_8") (pintype "power_in"))
      (node (ref "U2") (pin "17") (pinfunction "IO19_17") (pintype "bidirectional"))
    )
    (net (code "16") (name "INT_RTC") (class "Default")
      (node (ref "R1_PINH1") (pin "1") (pinfunction "1_1") (pintype "passive"))
      (node (ref "TP15") (pin "TP") (pinfunction "TP_TP") (pintype "input"))
      (node (ref "U2") (pin "8") (pinfunction "IO0_8") (pintype "bidirectional"))
      (node (ref "U3") (pin "3") (pinfunction "SQW/~{INT}_3") (pintype "output"))
    )
    (net (code "17") (name "IO{slash}BOOT") (class "Default")
      (node (ref "C6") (pin "1") (pinfunction "1_1") (pintype "passive"))
      (node (ref "R_BOOT") (pin "1") (pinfunction "1_1") (pintype "passive"))
      (node (ref "U$3") (pin "3") (pinfunction "3_3") (pintype "passive"))
      (node (ref "U$3") (pin "4") (pinfunction "4_4") (pintype "passive"))
      (node (ref "U2") (pin "15") (pinfunction "IO9_15") (pintype "bidirectional"))
    )
    (net (code "18") (name "IO{slash}CHANGE") (class "Default")
      (node (ref "C10") (pin "1") (pinfunction "1_1") (pintype "passive"))
      (node (ref "R_CHANGE") (pin "1") (pinfunction "1_1") (pintype "passive"))
      (node (ref "U$1") (pin "3") (pinfunction "3_3") (pintype "passive"))
      (node (ref "U$1") (pin "4") (pinfunction "4_4") (pintype "passive"))
      (node (ref "U2") (pin "23") (pinfunction "IO15_23") (pintype "bidirectional"))
    )
    (net (code "19") (name "MISO") (class "Default")
      (node (ref "D12") (pin "1") (pinfunction "1_1") (pintype "passive"))
      (node (ref "J4") (pin "P7") (pinfunction "DAT0_P7") (pintype "bidirectional"))
      (node (ref "R8") (pin "2") (pinfunction "2_2") (pintype "passive"))
      (node (ref "TP6") (pin "TP") (pinfunction "TP_TP") (pintype "input"))
      (node (ref "U1") (pin "2") (pinfunction "DO(IO1)_2") (pintype "bidirectional"))
      (node (ref "U2") (pin "27") (pinfunction "IO2_27") (pintype "bidirectional"))
    )
    (net (code "20") (name "MOSI") (class "Default")
      (node (ref "D11") (pin "1") (pinfunction "1_1") (pintype "passive"))
      (node (ref "J1") (pin "14") (pinfunction "14_14") (pintype "bidirectional"))
      (node (ref "J4") (pin "P3") (pinfunction "CMD_P3") (pintype "bidirectional"))
      (node (ref "R7") (pin "2") (pinfunction "2_2") (pintype "passive"))
      (node (ref "TP7") (pin "TP") (pinfunction "TP_TP") (pintype "input"))
      (node (ref "U1") (pin "5") (pinfunction "DI(IO0)_5") (pintype "bidirectional"))
      (node (ref "U2") (pin "7") (pinfunction "IO7_7") (pintype "bidirectional"))
    )
    (net (code "21") (name "Net-(CHG_LED-PadC)") (class "Default")
      (node (ref "CHG_LED") (pin "C") (pinfunction "C_C") (pintype "passive"))
      (node (ref "R1_BAT") (pin "2") (pinfunction "2_2") (pintype "passive"))
    )
    (net (code "22") (name "Net-(D2-CATHODE)") (class "Default")
      (node (ref "C1_BAT1") (pin "1") (pinfunction "1_1") (pintype "passive"))
      (node (ref "D2") (pin "1") (pinfunction "CATHODE_1") (pintype "bidirectional"))
      (node (ref "IC4") (pin "1") (pinfunction "VIN_1") (pintype "bidirectional"))
      (node (ref "IC4") (pin "3") (pinfunction "CE_3") (pintype "bidirectional"))
      (node (ref "Q1") (pin "2") (pinfunction "S_2") (pintype "bidirectional"))
    )
    (net (code "23") (name "Net-(D3-A)") (class "Default")
      (node (ref "C4") (pin "1") (pinfunction "1_1") (pintype "passive"))
      (node (ref "D3") (pin "2") (pinfunction "A_2") (pintype "bidirectional"))
      (node (ref "D4") (pin "1") (pinfunction "K_1") (pintype "bidirectional"))
    )
    (net (code "24") (name "Net-(D7-CATHODE)") (class "Default")
      (node (ref "D7") (pin "1") (pinfunction "CATHODE_1") (pintype "bidirectional"))
      (node (ref "R_CAPACITOR") (pin "1") (pinfunction "1_1") (pintype "passive"))
    )
    (net (code "25") (name "Net-(EPD_C1-Pad2)") (class "Default")
      (node (ref "EPD_C1") (pin "2") (pinfunction "2_2") (pintype "passive"))
      (node (ref "J1") (pin "4") (pinfunction "4_4") (pintype "bidirectional"))
    )
    (net (code "26") (name "Net-(EPD_C2-Pad2)") (class "Default")
      (node (ref "EPD_C2") (pin "2") (pinfunction "2_2") (pintype "passive"))
      (node (ref "J1") (pin "5") (pinfunction "5_5") (pintype "bidirectional"))
    )
    (net (code "27") (name "Net-(EPD_C6-Pad2)") (class "Default")
      (node (ref "EPD_C6") (pin "2") (pinfunction "2_2") (pintype "passive"))
      (node (ref "J1") (pin "18") (pinfunction "18_18") (pintype "bidirectional"))
    )
    (net (code "28") (name "Net-(EPD_C7-Pad2)") (class "Default")
      (node (ref "EPD_C7") (pin "2") (pinfunction "2_2") (pintype "passive"))
      (node (ref "J1") (pin "19") (pinfunction "19_19") (pintype "bidirectional"))
    )
    (net (code "29") (name "Net-(EPD_C8-Pad2)") (class "Default")
      (node (ref "EPD_C8") (pin "2") (pinfunction "2_2") (pintype "passive"))
      (node (ref "J1") (pin "20") (pinfunction "20_20") (pintype "bidirectional"))
    )
    (net (code "30") (name "Net-(EPD_C10-Pad2)") (class "Default")
      (node (ref "EPD_C10") (pin "2") (pinfunction "2_2") (pintype "passive"))
      (node (ref "J1") (pin "22") (pinfunction "22_22") (pintype "bidirectional"))
    )
    (net (code "31") (name "Net-(EPD_C12-Pad2)") (class "Default")
      (node (ref "EPD_C12") (pin "2") (pinfunction "2_2") (pintype "passive"))
      (node (ref "J1") (pin "24") (pinfunction "24_24") (pintype "bidirectional"))
    )
    (net (code "32") (name "Net-(IC1-CT)") (class "Default")
      (node (ref "C_DELAY") (pin "1") (pinfunction "1_1") (pintype "passive"))
      (node (ref "IC1") (pin "5") (pinfunction "CT_5") (pintype "bidirectional"))
    )
    (net (code "33") (name "Net-(J2-PadA5)") (class "Default")
      (node (ref "J2") (pin "A5") (pinfunction "A5_A5") (pintype "bidirectional"))
      (node (ref "R2-USB1") (pin "2") (pinfunction "2_2") (pintype "passive"))
    )
    (net (code "34") (name "Net-(J2-PadB5)") (class "Default")
      (node (ref "J2") (pin "B5") (pinfunction "B5_B5") (pintype "bidirectional"))
      (node (ref "R2-USB") (pin "1") (pinfunction "1_1") (pintype "passive"))
    )
    (net (code "35") (name "Net-(MCP73831-PROG)") (class "Default")
      (node (ref "MCP73831") (pin "5") (pinfunction "PROG_5") (pintype "input"))
      (node (ref "R2_BAT") (pin "2") (pinfunction "2_2") (pintype "passive"))
    )
    (net (code "36") (name "Net-(MCP73831-STAT)") (class "Default")
      (node (ref "MCP73831") (pin "1") (pinfunction "STAT_1") (pintype "output"))
      (node (ref "R1_BAT") (pin "1") (pinfunction "1_1") (pintype "passive"))
    )
    (net (code "37") (name "PREVGH") (class "Default")
      (node (ref "D5") (pin "1") (pinfunction "K_1") (pintype "bidirectional"))
      (node (ref "EPD_C9") (pin "2") (pinfunction "2_2") (pintype "passive"))
      (node (ref "J1") (pin "21") (pinfunction "21_21") (pintype "bidirectional"))
    )
    (net (code "38") (name "PREVGL") (class "Default")
      (node (ref "D4") (pin "2") (pinfunction "A_2") (pintype "bidirectional"))
      (node (ref "EPD_C11") (pin "2") (pinfunction "2_2") (pintype "passive"))
      (node (ref "J1") (pin "23") (pinfunction "23_23") (pintype "bidirectional"))
    )
    (net (code "39") (name "RESE") (class "Default")
      (node (ref "J1") (pin "3") (pinfunction "3_3") (pintype "bidirectional"))
      (node (ref "Q3") (pin "2") (pinfunction "S_2") (pintype "bidirectional"))
      (node (ref "R3") (pin "2") (pinfunction "2_2") (pintype "passive"))
    )
    (net (code "40") (name "RESE'") (class "Default")
      (node (ref "R2") (pin "2") (pinfunction "2_2") (pintype "passive"))
      (node (ref "R3") (pin "1") (pinfunction "1_1") (pintype "passive"))
      (node (ref "SJ1") (pin "2") (pinfunction "2_2") (pintype "passive"))
    )
    (net (code "41") (name "RESET") (class "Default")
      (node (ref "C5") (pin "1") (pinfunction "1_1") (pintype "passive"))
      (node (ref "IC1") (pin "1") (pinfunction "VOUT_1") (pintype "bidirectional"))
      (node (ref "RESET_BUTTON") (pin "3") (pinfunction "3_3") (pintype "passive"))
      (node (ref "RESET_BUTTON") (pin "4") (pinfunction "4_4") (pintype "passive"))
      (node (ref "R_RESET") (pin "1") (pinfunction "1_1") (pintype "passive"))
      (node (ref "U2") (pin "3") (pinfunction "EN_3") (pintype "input"))
    )
    (net (code "42") (name "RTC_RST") (class "Default")
      (node (ref "U2") (pin "16") (pinfunction "IO18_16") (pintype "bidirectional"))
      (node (ref "U3") (pin "4") (pinfunction "~{RST}_4") (pintype "input"))
    )
    (net (code "43") (name "RX") (class "Default")
      (node (ref "TP2") (pin "TP") (pinfunction "TP_TP") (pintype "input"))
      (node (ref "U2") (pin "24") (pinfunction "RXD0/GPIO17_24") (pintype "bidirectional"))
    )
    (net (code "44") (name "SCK") (class "Default")
      (node (ref "D10") (pin "1") (pinfunction "1_1") (pintype "passive"))
      (node (ref "J1") (pin "13") (pinfunction "13_13") (pintype "bidirectional"))
      (node (ref "J4") (pin "P5") (pinfunction "CLK_P5") (pintype "bidirectional"))
      (node (ref "R6") (pin "2") (pinfunction "2_2") (pintype "passive"))
      (node (ref "TP8") (pin "TP") (pinfunction "TP_TP") (pintype "input"))
      (node (ref "U1") (pin "6") (pinfunction "CLK_6") (pintype "input"))
      (node (ref "U2") (pin "6") (pinfunction "IO6_6") (pintype "bidirectional"))
    )
    (net (code "45") (name "SCL") (class "Default")
      (node (ref "J3") (pin "4") (pinfunction "4_4") (pintype "passive"))
      (node (ref "R2-PINH") (pin "1") (pinfunction "1_1") (pintype "passive"))
      (node (ref "SENSOR2") (pin "4") (pinfunction "SCK_4") (pintype "input"))
      (node (ref "U2") (pin "20") (pinfunction "IO22_20") (pintype "bidirectional"))
      (node (ref "U3") (pin "16") (pinfunction "SCL_16") (pintype "input"))
      (node (ref "U4") (pin "7") (pinfunction "SCL_7") (pintype "input"))
    )
    (net (code "46") (name "SDA") (class "Default")
      (node (ref "J3") (pin "3") (pinfunction "3_3") (pintype "passive"))
      (node (ref "R1_PINH") (pin "1") (pinfunction "1_1") (pintype "passive"))
      (node (ref "SENSOR2") (pin "3") (pinfunction "SDI_3") (pintype "bidirectional"))
      (node (ref "U2") (pin "19") (pinfunction "IO21_19") (pintype "bidirectional"))
      (node (ref "U3") (pin "15") (pinfunction "SDA_15") (pintype "bidirectional"))
      (node (ref "U4") (pin "8") (pinfunction "SDA_8") (pintype "bidirectional"))
    )
    (net (code "47") (name "SRC") (class "Default")
      (node (ref "C4") (pin "2") (pinfunction "2_2") (pintype "passive"))
      (node (ref "D5") (pin "2") (pinfunction "A_2") (pintype "bidirectional"))
      (node (ref "L1") (pin "1") (pinfunction "1_1") (pintype "passive"))
      (node (ref "Q3") (pin "3") (pinfunction "D_3") (pintype "bidirectional"))
    )
    (net (code "48") (name "SS_SD") (class "Default")
      (node (ref "D8") (pin "1") (pinfunction "1_1") (pintype "passive"))
      (node (ref "J4") (pin "P2") (pinfunction "CD/DAT3_P2") (pintype "bidirectional"))
      (node (ref "R10") (pin "2") (pinfunction "2_2") (pintype "passive"))
      (node (ref "U2") (pin "4") (pinfunction "IO4_4") (pintype "bidirectional"))
    )
    (net (code "49") (name "TX") (class "Default")
      (node (ref "TP1") (pin "TP") (pinfunction "TP_TP") (pintype "input"))
      (node (ref "U2") (pin "25") (pinfunction "TXD0/GPIO16_25") (pintype "bidirectional"))
    )
    (net (code "50") (name "USB_D+") (class "Default")
      (node (ref "D1") (pin "1") (pinfunction "I/O1_1_1") (pintype "bidirectional"))
      (node (ref "U2") (pin "14") (pinfunction "IO13_14") (pintype "bidirectional"))
    )
    (net (code "51") (name "USB_D-") (class "Default")
      (node (ref "D1") (pin "3") (pinfunction "I/O2_1_3") (pintype "bidirectional"))
      (node (ref "U2") (pin "13") (pinfunction "IO12_13") (pintype "bidirectional"))
    )
    (net (code "52") (name "VBAT") (class "Default")
      (node (ref "C2_BAT") (pin "1") (pinfunction "1_1") (pintype "passive"))
      (node (ref "MCP73831") (pin "3") (pinfunction "VBAT_3") (pintype "power_in"))
      (node (ref "Q1") (pin "3") (pinfunction "D_3") (pintype "bidirectional"))
      (node (ref "TP3") (pin "TP") (pinfunction "TP_TP") (pintype "input"))
      (node (ref "U4") (pin "2") (pinfunction "CELL_2") (pintype "power_in"))
      (node (ref "U4") (pin "3") (pinfunction "VDD_3") (pintype "power_in"))
    )
    (net (code "53") (name "VBUS") (class "Default")
      (node (ref "C1_BAT") (pin "1") (pinfunction "1_1") (pintype "passive"))
      (node (ref "C4_USB") (pin "1") (pinfunction "1_1") (pintype "passive"))
      (node (ref "C5_USB") (pin "1") (pinfunction "1_1") (pintype "passive"))
      (node (ref "CHG_LED") (pin "A") (pinfunction "A_A") (pintype "passive"))
      (node (ref "D1") (pin "5") (pinfunction "VBUS_5") (pintype "bidirectional"))
      (node (ref "D2") (pin "2") (pinfunction "ANODE_2") (pintype "bidirectional"))
      (node (ref "MCP73831") (pin "4") (pinfunction "VIN_4") (pintype "power_in"))
      (node (ref "PFMF.050.1") (pin "2") (pinfunction "2_2") (pintype "passive"))
      (node (ref "Q1") (pin "1") (pinfunction "G_1") (pintype "bidirectional"))
      (node (ref "R1_PWRUSB") (pin "1") (pinfunction "1_1") (pintype "passive"))
      (node (ref "TP14") (pin "TP") (pinfunction "TP_TP") (pintype "input"))
    )
    (net (code "54") (name "VRTC") (class "Default")
      (node (ref "C10_SUPERCAR") (pin "1") (pinfunction "1_1") (pintype "passive"))
      (node (ref "C8") (pin "1") (pinfunction "1_1") (pintype "passive"))
      (node (ref "R_CAPACITOR") (pin "2") (pinfunction "2_2") (pintype "passive"))
      (node (ref "U3") (pin "14") (pinfunction "VBAT_14") (pintype "power_in"))
    )
    (net (code "55") (name "VUSB") (class "Default")
      (node (ref "J2") (pin "A4") (pinfunction "A4_A4") (pintype "bidirectional"))
      (node (ref "J2") (pin "A9") (pinfunction "A9_A9") (pintype "bidirectional"))
      (node (ref "J2") (pin "B4") (pinfunction "B4_B4") (pintype "bidirectional"))
      (node (ref "J2") (pin "B9") (pinfunction "B9_B9") (pintype "bidirectional"))
      (node (ref "PFMF.050.1") (pin "1") (pinfunction "1_1") (pintype "passive"))
    )
    (net (code "56") (name "unconnected-(IC1-NC-Pad4)") (class "Default")
      (node (ref "IC1") (pin "4") (pinfunction "NC_4") (pintype "no_connect"))
    )
    (net (code "57") (name "unconnected-(IC4-NC-Pad4)") (class "Default")
      (node (ref "IC4") (pin "4") (pinfunction "NC_4") (pintype "no_connect"))
    )
    (net (code "58") (name "unconnected-(J1-Pad1)") (class "Default")
      (node (ref "J1") (pin "1") (pinfunction "1_1") (pintype "bidirectional"))
    )
    (net (code "59") (name "unconnected-(J1-Pad6)") (class "Default")
      (node (ref "J1") (pin "6") (pinfunction "6_6") (pintype "bidirectional"))
    )
    (net (code "60") (name "unconnected-(J1-Pad7)") (class "Default")
      (node (ref "J1") (pin "7") (pinfunction "7_7") (pintype "bidirectional"))
    )
    (net (code "61") (name "unconnected-(J2-PadA8)") (class "Default")
      (node (ref "J2") (pin "A8") (pinfunction "A8_A8") (pintype "bidirectional"))
    )
    (net (code "62") (name "unconnected-(J2-PadB8)") (class "Default")
      (node (ref "J2") (pin "B8") (pinfunction "B8_B8") (pintype "bidirectional"))
    )
    (net (code "63") (name "unconnected-(J4-DAT1-PadP8)") (class "Default")
      (node (ref "J4") (pin "P8") (pinfunction "DAT1_P8") (pintype "bidirectional"))
    )
    (net (code "64") (name "unconnected-(J4-DAT2-PadP1)") (class "Default")
      (node (ref "J4") (pin "P1") (pinfunction "DAT2_P1") (pintype "bidirectional"))
    )
    (net (code "65") (name "unconnected-(J4-DETECTION_1-PadS1)") (class "Default")
      (node (ref "J4") (pin "S1") (pinfunction "DETECTION_1_S1") (pintype "bidirectional"))
    )
    (net (code "66") (name "unconnected-(J4-DETECTION_2-PadS2)") (class "Default")
      (node (ref "J4") (pin "S2") (pinfunction "DETECTION_2_S2") (pintype "bidirectional"))
    )
    (net (code "67") (name "unconnected-(U2-NC-Pad22)") (class "Default")
      (node (ref "U2") (pin "22") (pinfunction "NC_22") (pintype "no_connect"))
    )
    (net (code "68") (name "unconnected-(U4-~{ALERT}-Pad5)") (class "Default")
      (node (ref "U4") (pin "5") (pinfunction "~{ALERT}_5") (pintype "output"))
    )
  )
)
